# LEDChannel.net
KiCad netlist of a schematic drawn in Altium Designer
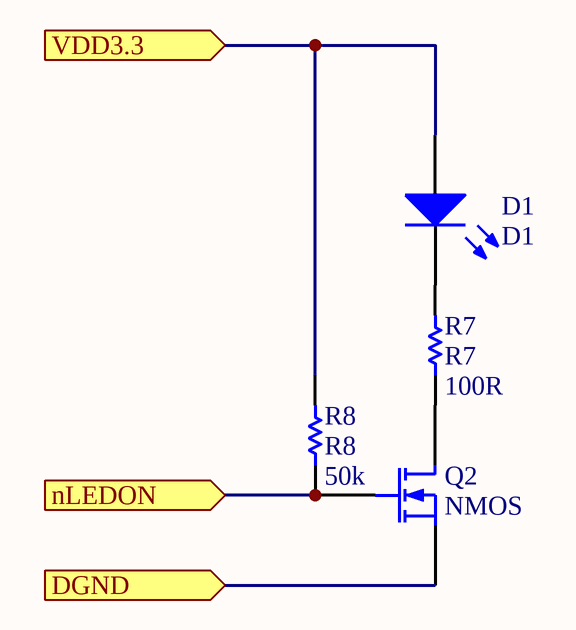
[diagram p0: LEDChannel.SchDoc]

(export (version "E")
  (design (tool "Eeschema 10.0.6"))
  (components
    (comp (ref "D1")
      (value "D1")
      (footprint "LED_0805_GREEN")
      (description "Typical INFRARED GaAs LED")
      (fields (field (name "PUBLISHER") "Altium Limited"))
      (libsource (lib "Miscellaneous Devices") (part "LED0"))
    )
    (comp (ref "Q2")
      (value "NMOS")
      (footprint "SOT23-3")
      (description "N-Channel MOSFET")
      (fields (field (name "PUBLISHER") "Altium Limited"))
      (libsource (lib "Miscellaneous Devices") (part "MOSFET-N"))
    )
    (comp (ref "R7")
      (value "R7")
      (footprint "RES_0805")
      (description "Resistor")
      (fields (field (name "ALTIUM_VALUE") "100R") (field (name "PUBLISHER") "Altium Limited"))
      (libsource (lib "Miscellaneous Devices") (part "Res1"))
    )
    (comp (ref "R8")
      (value "R8")
      (footprint "RES_0805")
      (description "Resistor")
      (fields (field (name "ALTIUM_VALUE") "50k") (field (name "PUBLISHER") "Altium Limited"))
      (libsource (lib "Miscellaneous Devices") (part "Res1"))
    )
  )
  (nets
    (net (code "1") (name "/DGND") (class "Default")
      (node (ref "Q2") (pin "3") (pinfunction "S_3") (pintype "passive"))
    )
    (net (code "2") (name "/VDD3.3") (class "Default")
      (node (ref "D1") (pin "1") (pinfunction "A_1") (pintype "passive"))
      (node (ref "R8") (pin "2") (pinfunction "2_2") (pintype "passive"))
    )
    (net (code "3") (name "/nLEDON") (class "Default")
      (node (ref "Q2") (pin "2") (pinfunction "G_2") (pintype "passive"))
      (node (ref "R8") (pin "1") (pinfunction "1_1") (pintype "passive"))
    )
    (net (code "4") (name "Net-(D1-K)") (class "Default")
      (node (ref "D1") (pin "2") (pinfunction "K_2") (pintype "passive"))
      (node (ref "R7") (pin "2") (pinfunction "2_2") (pintype "passive"))
    )
    (net (code "5") (name "Net-(Q2-D)") (class "Default")
      (node (ref "Q2") (pin "1") (pinfunction "D_1") (pintype "passive"))
      (node (ref "R7") (pin "1") (pinfunction "1_1") (pintype "passive"))
    )
  )
)
